# Terminada_v2_1.net
KiCad netlist of a schematic drawn in EAGLE
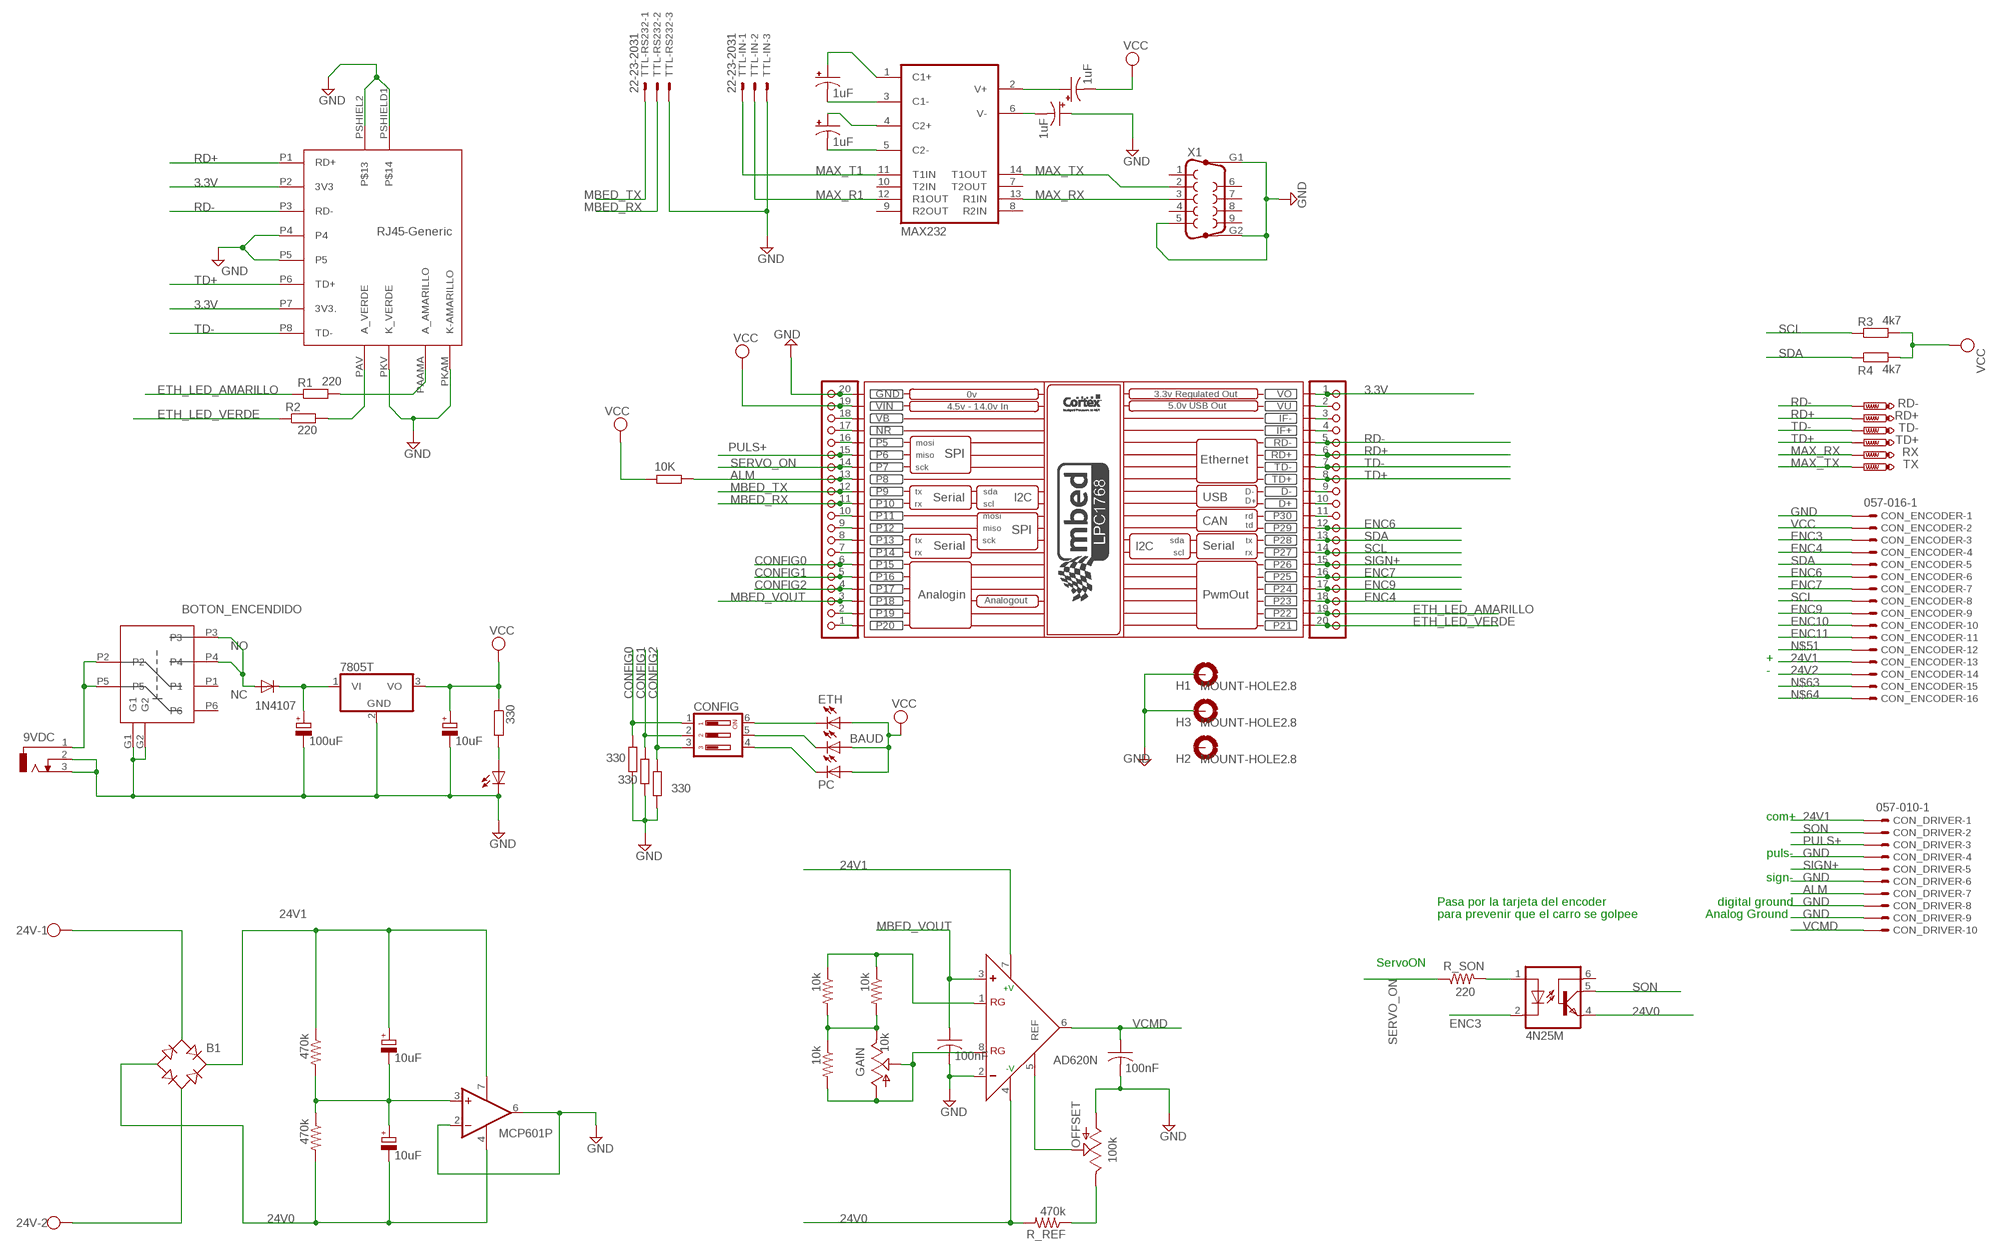
[diagram p0: schematic, sheet 1]

(export (version "E")
  (design (tool "Eeschema 10.0.6"))
  (components
    (comp (ref "9VDC")
      (value "DCJ0303")
      (footprint "eagle-import:DCJ0303")
      (libsource (lib "eagle-import") (part "DCJ0303"))
    )
    (comp (ref "24V")
      (value "W237-02P")
      (footprint "eagle-import:W237-132")
      (libsource (lib "eagle-import") (part "W237-02P"))
    )
    (comp (ref "B1")
      (value "RB1A")
      (footprint "eagle-import:RB1A")
      (libsource (lib "eagle-import") (part "RB1A"))
    )
    (comp (ref "BAUD")
      (value "LED3MM")
      (footprint "eagle-import:LED3MM")
      (libsource (lib "eagle-import") (part "LED3MM"))
    )
    (comp (ref "C1_+24")
      (value "10uF")
      (footprint "eagle-import:TT5D7")
      (libsource (lib "eagle-import") (part "CPOL-EUTT5D7"))
    )
    (comp (ref "C1_9V")
      (value "100uF")
      (footprint "eagle-import:TT5D7")
      (libsource (lib "eagle-import") (part "CPOL-EUTT5D7"))
    )
    (comp (ref "C1_MAX")
      (value "1uF")
      (footprint "eagle-import:E2,5-6E")
      (libsource (lib "eagle-import") (part "CPOL-USE2,5-6E"))
    )
    (comp (ref "C2_0V")
      (value "10uF")
      (footprint "eagle-import:TT5D7")
      (libsource (lib "eagle-import") (part "CPOL-EUTT5D7"))
    )
    (comp (ref "C2_9V")
      (value "10uF")
      (footprint "eagle-import:TT5D7")
      (libsource (lib "eagle-import") (part "CPOL-EUTT5D7"))
    )
    (comp (ref "C2_MAX")
      (value "1uF")
      (footprint "eagle-import:E2,5-6E")
      (libsource (lib "eagle-import") (part "CPOL-USE2,5-6E"))
    )
    (comp (ref "C3_AOUT")
      (value "100nF")
      (footprint "eagle-import:C025-024X044")
      (libsource (lib "eagle-import") (part "C-US025-024X044"))
    )
    (comp (ref "C3_MAX")
      (value "1uF")
      (footprint "eagle-import:E2,5-6E")
      (libsource (lib "eagle-import") (part "CPOL-USE2,5-6E"))
    )
    (comp (ref "C4_MAX")
      (value "1uF")
      (footprint "eagle-import:E2,5-6E")
      (libsource (lib "eagle-import") (part "CPOL-USE2,5-6E"))
    )
    (comp (ref "C5_AOUT")
      (value "100nF")
      (footprint "eagle-import:C025-024X044")
      (libsource (lib "eagle-import") (part "C-US025-024X044"))
    )
    (comp (ref "CONFIG")
      (value "DIP03YL")
      (footprint "eagle-import:DIP03YL")
      (libsource (lib "eagle-import") (part "DIP03YL"))
    )
    (comp (ref "CON_DRIVER")
      (value "057-010-1")
      (footprint "eagle-import:057-010-1")
      (libsource (lib "eagle-import") (part "057-010-1"))
    )
    (comp (ref "CON_ENCODER")
      (value "057-016-1")
      (footprint "eagle-import:057-016-1")
      (libsource (lib "eagle-import") (part "057-016-1"))
    )
    (comp (ref "D1_INPUT")
      (value "1N4107")
      (footprint "eagle-import:DO35-10")
      (libsource (lib "eagle-import") (part "1N4148DO35-10"))
    )
    (comp (ref "ETH")
      (value "LED3MM")
      (footprint "eagle-import:LED3MM")
      (libsource (lib "eagle-import") (part "LED3MM"))
    )
    (comp (ref "GAIN")
      (value "10k")
      (footprint "eagle-import:RJ9W")
      (libsource (lib "eagle-import") (part "TRIM_US-RJ9W"))
    )
    (comp (ref "H1")
      (value "MOUNT-HOLE2.8")
      (footprint "eagle-import:3,3-PAD")
      (libsource (lib "eagle-import") (part "MOUNT-PAD-ROUND3.3"))
    )
    (comp (ref "H2")
      (value "MOUNT-HOLE2.8")
      (footprint "eagle-import:3,3-PAD")
      (libsource (lib "eagle-import") (part "MOUNT-PAD-ROUND3.3"))
    )
    (comp (ref "H3")
      (value "MOUNT-HOLE2.8")
      (footprint "eagle-import:3,3-PAD")
      (libsource (lib "eagle-import") (part "MOUNT-PAD-ROUND3.3"))
    )
    (comp (ref "IC1")
      (value "MAX232")
      (footprint "eagle-import:DIL16")
      (libsource (lib "eagle-import") (part "MAX232"))
    )
    (comp (ref "IC2")
      (value "7805T")
      (footprint "eagle-import:TO220H")
      (libsource (lib "eagle-import") (part "78T05"))
    )
    (comp (ref "IC3")
      (value "MCP601P")
      (footprint "eagle-import:DIL08")
      (libsource (lib "eagle-import") (part "MCP601P"))
    )
    (comp (ref "IC4")
      (value "AD620N")
      (footprint "eagle-import:DIL08")
      (libsource (lib "eagle-import") (part "AD620N"))
    )
    (comp (ref "JP_LEFT")
      (value "PINHD-1X20")
      (footprint "eagle-import:1X20")
      (libsource (lib "eagle-import") (part "PINHD-1X20"))
    )
    (comp (ref "JP_RIGHT")
      (value "PINHD-1X20")
      (footprint "eagle-import:1X20")
      (libsource (lib "eagle-import") (part "PINHD-1X20"))
    )
    (comp (ref "KIT1")
      (value "MBED_NXP_LPC1768")
      (footprint "eagle-import:MBED-KIT")
      (libsource (lib "eagle-import") (part "MBED_NXP_LPC1768"))
    )
    (comp (ref "OFFSET")
      (value "100k")
      (footprint "eagle-import:RJ9W")
      (libsource (lib "eagle-import") (part "TRIM_US-RJ9W"))
    )
    (comp (ref "OK1")
      (value "4N25M")
      (footprint "eagle-import:DIL06")
      (libsource (lib "eagle-import") (part "4N?M25"))
    )
    (comp (ref "ON/OFF")
      (value "BOTON_ENCENDIDO")
      (footprint "eagle-import:BOTON_ENCNEDIDO")
      (libsource (lib "eagle-import") (part "BOTON_ENCENDIDO"))
    )
    (comp (ref "PC")
      (value "LED3MM")
      (footprint "eagle-import:LED3MM")
      (libsource (lib "eagle-import") (part "LED3MM"))
    )
    (comp (ref "POWER")
      (value "LED3MM")
      (footprint "eagle-import:LED3MM")
      (libsource (lib "eagle-import") (part "LED3MM"))
    )
    (comp (ref "PWR_LED_R")
      (value "330")
      (footprint "eagle-import:0204_7")
      (libsource (lib "eagle-import") (part "R-EU_0204/7"))
    )
    (comp (ref "R1")
      (value "220")
      (footprint "eagle-import:0207_15")
      (libsource (lib "eagle-import") (part "R-EU_0207/15"))
    )
    (comp (ref "R1_DIV")
      (value "470k")
      (footprint "eagle-import:0207_10")
      (libsource (lib "eagle-import") (part "resistor_R-US_0207/10"))
    )
    (comp (ref "R1_G")
      (value "10k")
      (footprint "eagle-import:0204_7")
      (libsource (lib "eagle-import") (part "resistor_R-US_0204/7"))
    )
    (comp (ref "R2")
      (value "220")
      (footprint "eagle-import:0207_15")
      (libsource (lib "eagle-import") (part "R-EU_0207/15"))
    )
    (comp (ref "R2_DIV")
      (value "470k")
      (footprint "eagle-import:0207_10")
      (libsource (lib "eagle-import") (part "resistor_R-US_0207/10"))
    )
    (comp (ref "R2_G")
      (value "10k")
      (footprint "eagle-import:0204_7")
      (libsource (lib "eagle-import") (part "resistor_R-US_0204/7"))
    )
    (comp (ref "R3")
      (value "4k7")
      (footprint "eagle-import:0204_7")
      (libsource (lib "eagle-import") (part "R-EU_0204/7"))
    )
    (comp (ref "R3_G")
      (value "10k")
      (footprint "eagle-import:0204_7")
      (libsource (lib "eagle-import") (part "resistor_R-US_0204/7"))
    )
    (comp (ref "R4")
      (value "4k7")
      (footprint "eagle-import:0204_7")
      (libsource (lib "eagle-import") (part "R-EU_0204/7"))
    )
    (comp (ref "R13")
      (value "330")
      (footprint "eagle-import:0204_7")
      (libsource (lib "eagle-import") (part "R-EU_0204/7"))
    )
    (comp (ref "R14")
      (value "330")
      (footprint "eagle-import:0204_7")
      (libsource (lib "eagle-import") (part "R-EU_0204/7"))
    )
    (comp (ref "R15")
      (value "330")
      (footprint "eagle-import:0204_7")
      (libsource (lib "eagle-import") (part "R-EU_0204/7"))
    )
    (comp (ref "R16_ALM")
      (value "10K")
      (footprint "eagle-import:0207_12")
      (libsource (lib "eagle-import") (part "R-EU_0207/12"))
    )
    (comp (ref "RD+")
      (value "PTR1PAD1-13Y")
      (footprint "eagle-import:P1-13Y")
      (libsource (lib "eagle-import") (part "PTR1PAD1-13Y"))
    )
    (comp (ref "RD-")
      (value "PTR1PAD1-13Y")
      (footprint "eagle-import:P1-13Y")
      (libsource (lib "eagle-import") (part "PTR1PAD1-13Y"))
    )
    (comp (ref "RX")
      (value "PTR1PAD1-13Y")
      (footprint "eagle-import:P1-13Y")
      (libsource (lib "eagle-import") (part "PTR1PAD1-13Y"))
    )
    (comp (ref "R_REF")
      (value "470k")
      (footprint "eagle-import:0204_7")
      (libsource (lib "eagle-import") (part "resistor_R-US_0204/7"))
    )
    (comp (ref "R_SON")
      (value "220")
      (footprint "eagle-import:0207_7")
      (libsource (lib "eagle-import") (part "R-US_0207/7"))
    )
    (comp (ref "TD+")
      (value "PTR1PAD1-13Y")
      (footprint "eagle-import:P1-13Y")
      (libsource (lib "eagle-import") (part "PTR1PAD1-13Y"))
    )
    (comp (ref "TD-")
      (value "PTR1PAD1-13Y")
      (footprint "eagle-import:P1-13Y")
      (libsource (lib "eagle-import") (part "PTR1PAD1-13Y"))
    )
    (comp (ref "TTL-IN")
      (value "22-23-2031")
      (footprint "eagle-import:22-23-2031")
      (fields (field (name "MF") "MOLEX"))
      (libsource (lib "eagle-import") (part "22-23-2031"))
    )
    (comp (ref "TTL-RS232")
      (value "22-23-2031")
      (footprint "eagle-import:22-23-2031")
      (fields (field (name "MF") "MOLEX"))
      (libsource (lib "eagle-import") (part "22-23-2031"))
    )
    (comp (ref "TX")
      (value "PTR1PAD1-13Y")
      (footprint "eagle-import:P1-13Y")
      (libsource (lib "eagle-import") (part "PTR1PAD1-13Y"))
    )
    (comp (ref "U$1")
      (value "RJ-45-GENERIC")
      (footprint "eagle-import:RJ45-GENERIC")
      (libsource (lib "eagle-import") (part "RJ-45-GENERIC"))
    )
    (comp (ref "X1")
      (value "F09HP")
      (footprint "eagle-import:F09HP")
      (libsource (lib "eagle-import") (part "F09HP"))
    )
  )
  (nets
    (net (code "1") (name "/3.3V") (class "Default")
      (node (ref "JP_RIGHT") (pin "1") (pinfunction "1_1") (pintype "passive"))
      (node (ref "KIT1") (pin "VOUT") (pinfunction "VO_VOUT") (pintype "power_in"))
      (node (ref "U$1") (pin "P2") (pinfunction "3V3_P2") (pintype "bidirectional"))
      (node (ref "U$1") (pin "P7") (pinfunction "3V3._P7") (pintype "bidirectional"))
    )
    (net (code "2") (name "/24V0") (class "Default")
      (node (ref "B1") (pin "-") (pinfunction "-_-") (pintype "passive"))
      (node (ref "C2_0V") (pin "-") (pinfunction "-_-") (pintype "passive"))
      (node (ref "IC3") (pin "4") (pinfunction "V-_4") (pintype "power_in"))
      (node (ref "IC4") (pin "4") (pinfunction "-V_4") (pintype "power_in"))
      (node (ref "OK1") (pin "4") (pinfunction "EMI_4") (pintype "passive"))
      (node (ref "R2_DIV") (pin "2") (pinfunction "2_2") (pintype "passive"))
      (node (ref "R_REF") (pin "2") (pinfunction "2_2") (pintype "passive"))
    )
    (net (code "3") (name "/24V1") (class "Default")
      (node (ref "B1") (pin "+") (pinfunction "+_+") (pintype "passive"))
      (node (ref "C1_+24") (pin "+") (pinfunction "+_+") (pintype "passive"))
      (node (ref "CON_DRIVER") (pin "1") (pinfunction "S_1") (pintype "passive"))
      (node (ref "CON_ENCODER") (pin "13") (pinfunction "S_13") (pintype "passive"))
      (node (ref "IC3") (pin "7") (pinfunction "V+_7") (pintype "power_in"))
      (node (ref "IC4") (pin "7") (pinfunction "+V_7") (pintype "power_in"))
      (node (ref "R1_DIV") (pin "1") (pinfunction "1_1") (pintype "passive"))
    )
    (net (code "4") (name "/24V2") (class "Default")
      (node (ref "CON_ENCODER") (pin "14") (pinfunction "S_14") (pintype "passive"))
    )
    (net (code "5") (name "/ALM") (class "Default")
      (node (ref "CON_DRIVER") (pin "7") (pinfunction "S_7") (pintype "passive"))
      (node (ref "JP_LEFT") (pin "13") (pinfunction "13_13") (pintype "passive"))
      (node (ref "KIT1") (pin "P$8") (pinfunction "P8_P$8") (pintype "bidirectional"))
      (node (ref "R16_ALM") (pin "1") (pinfunction "1_1") (pintype "passive"))
    )
    (net (code "6") (name "/CONFIG0") (class "Default")
      (node (ref "CONFIG") (pin "1") (pinfunction "1_1") (pintype "passive"))
      (node (ref "JP_LEFT") (pin "6") (pinfunction "6_6") (pintype "passive"))
      (node (ref "KIT1") (pin "P$15") (pinfunction "P15_P$15") (pintype "bidirectional"))
      (node (ref "R15") (pin "2") (pinfunction "2_2") (pintype "passive"))
    )
    (net (code "7") (name "/CONFIG1") (class "Default")
      (node (ref "CONFIG") (pin "2") (pinfunction "2_2") (pintype "passive"))
      (node (ref "JP_LEFT") (pin "5") (pinfunction "5_5") (pintype "passive"))
      (node (ref "KIT1") (pin "P$16") (pinfunction "P16_P$16") (pintype "bidirectional"))
      (node (ref "R14") (pin "2") (pinfunction "2_2") (pintype "passive"))
    )
    (net (code "8") (name "/CONFIG2") (class "Default")
      (node (ref "CONFIG") (pin "3") (pinfunction "3_3") (pintype "passive"))
      (node (ref "JP_LEFT") (pin "4") (pinfunction "4_4") (pintype "passive"))
      (node (ref "KIT1") (pin "P$17") (pinfunction "P17_P$17") (pintype "bidirectional"))
      (node (ref "R13") (pin "2") (pinfunction "2_2") (pintype "passive"))
    )
    (net (code "9") (name "/ENC3") (class "Default")
      (node (ref "CON_ENCODER") (pin "3") (pinfunction "S_3") (pintype "passive"))
      (node (ref "OK1") (pin "2") (pinfunction "C_2") (pintype "passive"))
    )
    (net (code "10") (name "/ENC4") (class "Default")
      (node (ref "CON_ENCODER") (pin "4") (pinfunction "S_4") (pintype "passive"))
      (node (ref "JP_RIGHT") (pin "18") (pinfunction "18_18") (pintype "passive"))
      (node (ref "KIT1") (pin "P$23") (pinfunction "P23_P$23") (pintype "bidirectional"))
    )
    (net (code "11") (name "/ENC6") (class "Default")
      (node (ref "CON_ENCODER") (pin "6") (pinfunction "S_6") (pintype "passive"))
      (node (ref "JP_RIGHT") (pin "12") (pinfunction "12_12") (pintype "passive"))
      (node (ref "KIT1") (pin "P$29") (pinfunction "P29_P$29") (pintype "bidirectional"))
    )
    (net (code "12") (name "/ENC7") (class "Default")
      (node (ref "CON_ENCODER") (pin "7") (pinfunction "S_7") (pintype "passive"))
      (node (ref "JP_RIGHT") (pin "16") (pinfunction "16_16") (pintype "passive"))
      (node (ref "KIT1") (pin "P$25") (pinfunction "P25_P$25") (pintype "bidirectional"))
    )
    (net (code "13") (name "/ENC9") (class "Default")
      (node (ref "CON_ENCODER") (pin "9") (pinfunction "S_9") (pintype "passive"))
      (node (ref "JP_RIGHT") (pin "17") (pinfunction "17_17") (pintype "passive"))
      (node (ref "KIT1") (pin "P$24") (pinfunction "P24_P$24") (pintype "bidirectional"))
    )
    (net (code "14") (name "/ENC10") (class "Default")
      (node (ref "CON_ENCODER") (pin "10") (pinfunction "S_10") (pintype "passive"))
    )
    (net (code "15") (name "/ENC11") (class "Default")
      (node (ref "CON_ENCODER") (pin "11") (pinfunction "S_11") (pintype "passive"))
    )
    (net (code "16") (name "/ETH_LED_AMARILLO") (class "Default")
      (node (ref "JP_RIGHT") (pin "19") (pinfunction "19_19") (pintype "passive"))
      (node (ref "KIT1") (pin "P$22") (pinfunction "P22_P$22") (pintype "bidirectional"))
      (node (ref "R1") (pin "1") (pinfunction "1_1") (pintype "passive"))
    )
    (net (code "17") (name "/ETH_LED_VERDE") (class "Default")
      (node (ref "JP_RIGHT") (pin "20") (pinfunction "20_20") (pintype "passive"))
      (node (ref "KIT1") (pin "P$21") (pinfunction "P21_P$21") (pintype "bidirectional"))
      (node (ref "R2") (pin "1") (pinfunction "1_1") (pintype "passive"))
    )
    (net (code "18") (name "/MAX_R1") (class "Default")
      (node (ref "IC1") (pin "12") (pinfunction "R1OUT_12") (pintype "output"))
      (node (ref "TTL-IN") (pin "2") (pinfunction "S_2") (pintype "passive"))
    )
    (net (code "19") (name "/MAX_RX") (class "Default")
      (node (ref "IC1") (pin "13") (pinfunction "R1IN_13") (pintype "input"))
      (node (ref "RX") (pin "TP") (pinfunction "TP_TP") (pintype "input"))
      (node (ref "X1") (pin "3") (pinfunction "3_3") (pintype "passive"))
    )
    (net (code "20") (name "/MAX_T1") (class "Default")
      (node (ref "IC1") (pin "11") (pinfunction "T1IN_11") (pintype "input"))
      (node (ref "TTL-IN") (pin "1") (pinfunction "S_1") (pintype "passive"))
    )
    (net (code "21") (name "/MAX_TX") (class "Default")
      (node (ref "IC1") (pin "14") (pinfunction "T1OUT_14") (pintype "output"))
      (node (ref "TX") (pin "TP") (pinfunction "TP_TP") (pintype "input"))
      (node (ref "X1") (pin "2") (pinfunction "2_2") (pintype "passive"))
    )
    (net (code "22") (name "/MBED_RX") (class "Default")
      (node (ref "JP_LEFT") (pin "11") (pinfunction "11_11") (pintype "passive"))
      (node (ref "KIT1") (pin "P$10") (pinfunction "P10_P$10") (pintype "bidirectional"))
      (node (ref "TTL-RS232") (pin "2") (pinfunction "S_2") (pintype "passive"))
    )
    (net (code "23") (name "/MBED_TX") (class "Default")
      (node (ref "JP_LEFT") (pin "12") (pinfunction "12_12") (pintype "passive"))
      (node (ref "KIT1") (pin "P$9") (pinfunction "P9_P$9") (pintype "bidirectional"))
      (node (ref "TTL-RS232") (pin "1") (pinfunction "S_1") (pintype "passive"))
    )
    (net (code "24") (name "/MBED_VOUT") (class "Default")
      (node (ref "C5_AOUT") (pin "1") (pinfunction "1_1") (pintype "passive"))
      (node (ref "IC4") (pin "3") (pinfunction "+_3") (pintype "input"))
      (node (ref "JP_LEFT") (pin "3") (pinfunction "3_3") (pintype "passive"))
      (node (ref "KIT1") (pin "P$18") (pinfunction "P18_P$18") (pintype "bidirectional"))
    )
    (net (code "25") (name "/N$51") (class "Default")
      (node (ref "CON_ENCODER") (pin "12") (pinfunction "S_12") (pintype "passive"))
    )
    (net (code "26") (name "/N$63") (class "Default")
      (node (ref "CON_ENCODER") (pin "15") (pinfunction "S_15") (pintype "passive"))
    )
    (net (code "27") (name "/N$64") (class "Default")
      (node (ref "CON_ENCODER") (pin "16") (pinfunction "S_16") (pintype "passive"))
    )
    (net (code "28") (name "/PULS+") (class "Default")
      (node (ref "CON_DRIVER") (pin "3") (pinfunction "S_3") (pintype "passive"))
      (node (ref "JP_LEFT") (pin "15") (pinfunction "15_15") (pintype "passive"))
      (node (ref "KIT1") (pin "P$6") (pinfunction "P6_P$6") (pintype "bidirectional"))
    )
    (net (code "29") (name "/RD+") (class "Default")
      (node (ref "JP_RIGHT") (pin "6") (pinfunction "6_6") (pintype "passive"))
      (node (ref "KIT1") (pin "RD+") (pinfunction "RD+_RD+") (pintype "bidirectional"))
      (node (ref "RD+") (pin "TP") (pinfunction "TP_TP") (pintype "input"))
      (node (ref "U$1") (pin "P1") (pinfunction "RD+_P1") (pintype "bidirectional"))
    )
    (net (code "30") (name "/RD-") (class "Default")
      (node (ref "JP_RIGHT") (pin "5") (pinfunction "5_5") (pintype "passive"))
      (node (ref "KIT1") (pin "RD-") (pinfunction "RD-_RD-") (pintype "bidirectional"))
      (node (ref "RD-") (pin "TP") (pinfunction "TP_TP") (pintype "input"))
      (node (ref "U$1") (pin "P3") (pinfunction "RD-_P3") (pintype "bidirectional"))
    )
    (net (code "31") (name "/SCL") (class "Default")
      (node (ref "CON_ENCODER") (pin "8") (pinfunction "S_8") (pintype "passive"))
      (node (ref "JP_RIGHT") (pin "14") (pinfunction "14_14") (pintype "passive"))
      (node (ref "KIT1") (pin "P$27") (pinfunction "P27_P$27") (pintype "bidirectional"))
      (node (ref "R3") (pin "1") (pinfunction "1_1") (pintype "passive"))
    )
    (net (code "32") (name "/SDA") (class "Default")
      (node (ref "CON_ENCODER") (pin "5") (pinfunction "S_5") (pintype "passive"))
      (node (ref "JP_RIGHT") (pin "13") (pinfunction "13_13") (pintype "passive"))
      (node (ref "KIT1") (pin "P$28") (pinfunction "P28_P$28") (pintype "bidirectional"))
      (node (ref "R4") (pin "1") (pinfunction "1_1") (pintype "passive"))
    )
    (net (code "33") (name "/SERVO_ON") (class "Default")
      (node (ref "JP_LEFT") (pin "14") (pinfunction "14_14") (pintype "passive"))
      (node (ref "KIT1") (pin "P$7") (pinfunction "P7_P$7") (pintype "bidirectional"))
      (node (ref "R_SON") (pin "1") (pinfunction "1_1") (pintype "passive"))
    )
    (net (code "34") (name "/SIGN+") (class "Default")
      (node (ref "CON_DRIVER") (pin "5") (pinfunction "S_5") (pintype "passive"))
      (node (ref "JP_RIGHT") (pin "15") (pinfunction "15_15") (pintype "passive"))
      (node (ref "KIT1") (pin "P$26") (pinfunction "P26_P$26") (pintype "bidirectional"))
    )
    (net (code "35") (name "/SON") (class "Default")
      (node (ref "CON_DRIVER") (pin "2") (pinfunction "S_2") (pintype "passive"))
      (node (ref "OK1") (pin "5") (pinfunction "COL_5") (pintype "passive"))
    )
    (net (code "36") (name "/TD+") (class "Default")
      (node (ref "JP_RIGHT") (pin "8") (pinfunction "8_8") (pintype "passive"))
      (node (ref "KIT1") (pin "TD+") (pinfunction "TD+_TD+") (pintype "bidirectional"))
      (node (ref "TD+") (pin "TP") (pinfunction "TP_TP") (pintype "input"))
      (node (ref "U$1") (pin "P6") (pinfunction "TD+_P6") (pintype "bidirectional"))
    )
    (net (code "37") (name "/TD-") (class "Default")
      (node (ref "JP_RIGHT") (pin "7") (pinfunction "7_7") (pintype "passive"))
      (node (ref "KIT1") (pin "TD-") (pinfunction "TD-_TD-") (pintype "bidirectional"))
      (node (ref "TD-") (pin "TP") (pinfunction "TP_TP") (pintype "input"))
      (node (ref "U$1") (pin "P8") (pinfunction "TD-_P8") (pintype "bidirectional"))
    )
    (net (code "38") (name "/VCMD") (class "Default")
      (node (ref "C3_AOUT") (pin "1") (pinfunction "1_1") (pintype "passive"))
      (node (ref "CON_DRIVER") (pin "10") (pinfunction "S_10") (pintype "passive"))
      (node (ref "IC4") (pin "6") (pinfunction "OUT_6") (pintype "output"))
    )
    (net (code "39") (name "GND") (class "Default")
      (node (ref "9VDC") (pin "2") (pinfunction "2_2") (pintype "passive"))
      (node (ref "9VDC") (pin "3") (pinfunction "3_3") (pintype "passive"))
      (node (ref "C1_9V") (pin "-") (pinfunction "-_-") (pintype "passive"))
      (node (ref "C2_9V") (pin "-") (pinfunction "-_-") (pintype "passive"))
      (node (ref "C3_AOUT") (pin "2") (pinfunction "2_2") (pintype "passive"))
      (node (ref "C3_MAX") (pin "+") (pinfunction "+_+") (pintype "passive"))
      (node (ref "C5_AOUT") (pin "2") (pinfunction "2_2") (pintype "passive"))
      (node (ref "CON_DRIVER") (pin "4") (pinfunction "S_4") (pintype "passive"))
      (node (ref "CON_DRIVER") (pin "6") (pinfunction "S_6") (pintype "passive"))
      (node (ref "CON_DRIVER") (pin "8") (pinfunction "S_8") (pintype "passive"))
      (node (ref "CON_DRIVER") (pin "9") (pinfunction "S_9") (pintype "passive"))
      (node (ref "CON_ENCODER") (pin "1") (pinfunction "S_1") (pintype "passive"))
      (node (ref "H1") (pin "B3,3") (pinfunction "MOUNT_B3,3") (pintype "passive"))
      (node (ref "H3") (pin "B3,3") (pinfunction "MOUNT_B3,3") (pintype "passive"))
      (node (ref "IC2") (pin "2") (pinfunction "GND_2") (pintype "passive"))
      (node (ref "IC3") (pin "2") (pinfunction "-IN_2") (pintype "input"))
      (node (ref "IC3") (pin "6") (pinfunction "OUT_6") (pintype "output"))
      (node (ref "IC4") (pin "2") (pinfunction "-_2") (pintype "input"))
      (node (ref "JP_LEFT") (pin "20") (pinfunction "20_20") (pintype "passive"))
      (node (ref "KIT1") (pin "GND") (pinfunction "GND_GND") (pintype "power_in"))
      (node (ref "OFFSET") (pin "A") (pinfunction "A_A") (pintype "passive"))
      (node (ref "ON/OFF") (pin "G1") (pinfunction "G1_G1") (pintype "bidirectional"))
      (node (ref "ON/OFF") (pin "G2") (pinfunction "G2_G2") (pintype "bidirectional"))
      (node (ref "POWER") (pin "K") (pinfunction "C_K") (pintype "passive"))
      (node (ref "R13") (pin "1") (pinfunction "1_1") (pintype "passive"))
      (node (ref "R14") (pin "1") (pinfunction "1_1") (pintype "passive"))
      (node (ref "R15") (pin "1") (pinfunction "1_1") (pintype "passive"))
      (node (ref "TTL-IN") (pin "3") (pinfunction "S_3") (pintype "passive"))
      (node (ref "TTL-RS232") (pin "3") (pinfunction "S_3") (pintype "passive"))
      (node (ref "U$1") (pin "P4") (pinfunction "P4_P4") (pintype "bidirectional"))
      (node (ref "U$1") (pin "P5") (pinfunction "P5_P5") (pintype "bidirectional"))
      (node (ref "U$1") (pin "PKAM") (pinfunction "K-AMARILLO_PKAM") (pintype "bidirectional"))
      (node (ref "U$1") (pin "PKV") (pinfunction "K_VERDE_PKV") (pintype "bidirectional"))
      (node (ref "U$1") (pin "PSHIEL2") (pinfunction "P$13_PSHIEL2") (pintype "bidirectional"))
      (node (ref "U$1") (pin "PSHIELD1") (pinfunction "P$14_PSHIELD1") (pintype "bidirectional"))
      (node (ref "X1") (pin "5") (pinfunction "5_5") (pintype "passive"))
      (node (ref "X1") (pin "G1") (pinfunction "G1_G1") (pintype "passive"))
      (node (ref "X1") (pin "G2") (pinfunction "G2_G2") (pintype "passive"))
    )
    (net (code "40") (name "Net-(9VDC-Pad1)") (class "Default")
      (node (ref "9VDC") (pin "1") (pinfunction "1_1") (pintype "passive"))
      (node (ref "ON/OFF") (pin "P2") (pinfunction "P2_P2") (pintype "bidirectional"))
      (node (ref "ON/OFF") (pin "P5") (pinfunction "P5_P5") (pintype "bidirectional"))
    )
    (net (code "41") (name "Net-(24VA-KL)") (class "Default")
      (node (ref "24V") (pin "1") (pinfunction "KL_1") (pintype "passive"))
      (node (ref "B1") (pin "AC1") (pinfunction "AC1_AC1") (pintype "passive"))
    )
    (net (code "42") (name "Net-(24VB-KL)") (class "Default")
      (node (ref "24V") (pin "2") (pinfunction "KL_2") (pintype "passive"))
      (node (ref "B1") (pin "AC2") (pinfunction "AC2_AC2") (pintype "passive"))
    )
    (net (code "43") (name "Net-(BAUD-C)") (class "Default")
      (node (ref "BAUD") (pin "K") (pinfunction "C_K") (pintype "passive"))
      (node (ref "CONFIG") (pin "5") (pinfunction "5_5") (pintype "passive"))
    )
    (net (code "44") (name "Net-(D1_INPUT-PadA)") (class "Default")
      (node (ref "D1_INPUT") (pin "A") (pinfunction "A_A") (pintype "passive"))
      (node (ref "ON/OFF") (pin "P3") (pinfunction "P3_P3") (pintype "bidirectional"))
      (node (ref "ON/OFF") (pin "P4") (pinfunction "P4_P4") (pintype "bidirectional"))
    )
    (net (code "45") (name "Net-(ETH-C)") (class "Default")
      (node (ref "CONFIG") (pin "6") (pinfunction "6_6") (pintype "passive"))
      (node (ref "ETH") (pin "K") (pinfunction "C_K") (pintype "passive"))
    )
    (net (code "46") (name "Net-(GAIN-PadA)") (class "Default")
      (node (ref "GAIN") (pin "A") (pinfunction "A_A") (pintype "passive"))
      (node (ref "GAIN") (pin "S") (pinfunction "S_S") (pintype "passive"))
      (node (ref "IC4") (pin "8") (pinfunction "RG_8") (pintype "passive"))
      (node (ref "R2_G") (pin "2") (pinfunction "2_2") (pintype "passive"))
    )
    (net (code "47") (name "Net-(GAIN-PadE)") (class "Default")
      (node (ref "GAIN") (pin "E") (pinfunction "E_E") (pintype "passive"))
      (node (ref "R1_G") (pin "2") (pinfunction "2_2") (pintype "passive"))
      (node (ref "R2_G") (pin "1") (pinfunction "1_1") (pintype "passive"))
      (node (ref "R3_G") (pin "2") (pinfunction "2_2") (pintype "passive"))
    )
    (net (code "48") (name "Net-(IC1A-C1+)") (class "Default")
      (node (ref "C1_MAX") (pin "+") (pinfunction "+_+") (pintype "passive"))
      (node (ref "IC1") (pin "1") (pinfunction "C1+_1") (pintype "bidirectional"))
    )
    (net (code "49") (name "Net-(IC1A-C1-)") (class "Default")
      (node (ref "C1_MAX") (pin "-") (pinfunction "-_-") (pintype "passive"))
      (node (ref "IC1") (pin "3") (pinfunction "C1-_3") (pintype "bidirectional"))
    )
    (net (code "50") (name "Net-(IC1A-C2+)") (class "Default")
      (node (ref "C2_MAX") (pin "+") (pinfunction "+_+") (pintype "passive"))
      (node (ref "IC1") (pin "4") (pinfunction "C2+_4") (pintype "bidirectional"))
    )
    (net (code "51") (name "Net-(IC1A-C2-)") (class "Default")
      (node (ref "C2_MAX") (pin "-") (pinfunction "-_-") (pintype "passive"))
      (node (ref "IC1") (pin "5") (pinfunction "C2-_5") (pintype "bidirectional"))
    )
    (net (code "52") (name "Net-(IC1A-V+)") (class "Default")
      (node (ref "C4_MAX") (pin "+") (pinfunction "+_+") (pintype "passive"))
      (node (ref "IC1") (pin "2") (pinfunction "V+_2") (pintype "bidirectional"))
    )
    (net (code "53") (name "Net-(IC1A-V-)") (class "Default")
      (node (ref "C3_MAX") (pin "-") (pinfunction "-_-") (pintype "passive"))
      (node (ref "IC1") (pin "6") (pinfunction "V-_6") (pintype "bidirectional"))
    )
    (net (code "54") (name "Net-(IC2-VI)") (class "Default")
      (node (ref "C1_9V") (pin "+") (pinfunction "+_+") (pintype "passive"))
      (node (ref "D1_INPUT") (pin "C") (pinfunction "C_C") (pintype "passive"))
      (node (ref "IC2") (pin "1") (pinfunction "VI_1") (pintype "input"))
    )
    (net (code "55") (name "Net-(IC3-+IN)") (class "Default")
      (node (ref "C1_+24") (pin "-") (pinfunction "-_-") (pintype "passive"))
      (node (ref "C2_0V") (pin "+") (pinfunction "+_+") (pintype "passive"))
      (node (ref "IC3") (pin "3") (pinfunction "+IN_3") (pintype "input"))
      (node (ref "R1_DIV") (pin "2") (pinfunction "2_2") (pintype "passive"))
      (node (ref "R2_DIV") (pin "1") (pinfunction "1_1") (pintype "passive"))
    )
    (net (code "56") (name "Net-(IC4-REF)") (class "Default")
      (node (ref "IC4") (pin "5") (pinfunction "REF_5") (pintype "passive"))
      (node (ref "OFFSET") (pin "S") (pinfunction "S_S") (pintype "passive"))
    )
    (net (code "57") (name "Net-(IC4-RG-Pad1)") (class "Default")
      (node (ref "IC4") (pin "1") (pinfunction "RG_1") (pintype "passive"))
      (node (ref "R1_G") (pin "1") (pinfunction "1_1") (pintype "passive"))
      (node (ref "R3_G") (pin "1") (pinfunction "1_1") (pintype "passive"))
    )
    (net (code "58") (name "Net-(JP_LEFT-Pad17)") (class "Default")
      (node (ref "JP_LEFT") (pin "17") (pinfunction "17_17") (pintype "passive"))
      (node (ref "KIT1") (pin "NR") (pinfunction "NR_NR") (pintype "power_in"))
    )
    (net (code "59") (name "Net-(JP_LEFT-Pad18)") (class "Default")
      (node (ref "JP_LEFT") (pin "18") (pinfunction "18_18") (pintype "passive"))
      (node (ref "KIT1") (pin "VB") (pinfunction "VB_VB") (pintype "power_in"))
    )
    (net (code "60") (name "Net-(JP_RIGHT-Pad2)") (class "Default")
      (node (ref "JP_RIGHT") (pin "2") (pinfunction "2_2") (pintype "passive"))
      (node (ref "KIT1") (pin "VU") (pinfunction "VU_VU") (pintype "power_in"))
    )
    (net (code "61") (name "Net-(JP_RIGHT-Pad3)") (class "Default")
      (node (ref "JP_RIGHT") (pin "3") (pinfunction "3_3") (pintype "passive"))
      (node (ref "KIT1") (pin "IF-") (pinfunction "IF-_IF-") (pintype "bidirectional"))
    )
    (net (code "62") (name "Net-(JP_RIGHT-Pad4)") (class "Default")
      (node (ref "JP_RIGHT") (pin "4") (pinfunction "4_4") (pintype "passive"))
      (node (ref "KIT1") (pin "IF+") (pinfunction "IF+_IF+") (pintype "bidirectional"))
    )
    (net (code "63") (name "Net-(JP_RIGHT-Pad9)") (class "Default")
      (node (ref "JP_RIGHT") (pin "9") (pinfunction "9_9") (pintype "passive"))
      (node (ref "KIT1") (pin "D-") (pinfunction "D-_D-") (pintype "bidirectional"))
    )
    (net (code "64") (name "Net-(JP_RIGHT-Pad10)") (class "Default")
      (node (ref "JP_RIGHT") (pin "10") (pinfunction "10_10") (pintype "passive"))
      (node (ref "KIT1") (pin "D+") (pinfunction "D+_D+") (pintype "bidirectional"))
    )
    (net (code "65") (name "Net-(KIT1-P5)") (class "Default")
      (node (ref "JP_LEFT") (pin "16") (pinfunction "16_16") (pintype "passive"))
      (node (ref "KIT1") (pin "P$5") (pinfunction "P5_P$5") (pintype "bidirectional"))
    )
    (net (code "66") (name "Net-(KIT1-P11)") (class "Default")
      (node (ref "JP_LEFT") (pin "10") (pinfunction "10_10") (pintype "passive"))
      (node (ref "KIT1") (pin "P$11") (pinfunction "P11_P$11") (pintype "bidirectional"))
    )
    (net (code "67") (name "Net-(KIT1-P12)") (class "Default")
      (node (ref "JP_LEFT") (pin "9") (pinfunction "9_9") (pintype "passive"))
      (node (ref "KIT1") (pin "P$12") (pinfunction "P12_P$12") (pintype "bidirectional"))
    )
    (net (code "68") (name "Net-(KIT1-P13)") (class "Default")
      (node (ref "JP_LEFT") (pin "8") (pinfunction "8_8") (pintype "passive"))
      (node (ref "KIT1") (pin "P$13") (pinfunction "P13_P$13") (pintype "bidirectional"))
    )
    (net (code "69") (name "Net-(KIT1-P14)") (class "Default")
      (node (ref "JP_LEFT") (pin "7") (pinfunction "7_7") (pintype "passive"))
      (node (ref "KIT1") (pin "P$14") (pinfunction "P14_P$14") (pintype "bidirectional"))
    )
    (net (code "70") (name "Net-(KIT1-P19)") (class "Default")
      (node (ref "JP_LEFT") (pin "2") (pinfunction "2_2") (pintype "passive"))
      (node (ref "KIT1") (pin "P$19") (pinfunction "P19_P$19") (pintype "bidirectional"))
    )
    (net (code "71") (name "Net-(KIT1-P20)") (class "Default")
      (node (ref "JP_LEFT") (pin "1") (pinfunction "1_1") (pintype "passive"))
      (node (ref "KIT1") (pin "P$20") (pinfunction "P20_P$20") (pintype "bidirectional"))
    )
    (net (code "72") (name "Net-(KIT1-P30)") (class "Default")
      (node (ref "JP_RIGHT") (pin "11") (pinfunction "11_11") (pintype "passive"))
      (node (ref "KIT1") (pin "P$30") (pinfunction "P30_P$30") (pintype "bidirectional"))
    )
    (net (code "73") (name "Net-(OFFSET-PadE)") (class "Default")
      (node (ref "OFFSET") (pin "E") (pinfunction "E_E") (pintype "passive"))
      (node (ref "R_REF") (pin "1") (pinfunction "1_1") (pintype "passive"))
    )
    (net (code "74") (name "Net-(OK1-A)") (class "Default")
      (node (ref "OK1") (pin "1") (pinfunction "A_1") (pintype "passive"))
      (node (ref "R_SON") (pin "2") (pinfunction "2_2") (pintype "passive"))
    )
    (net (code "75") (name "Net-(PC-C)") (class "Default")
      (node (ref "CONFIG") (pin "4") (pinfunction "4_4") (pintype "passive"))
      (node (ref "PC") (pin "K") (pinfunction "C_K") (pintype "passive"))
    )
    (net (code "76") (name "Net-(POWER-PadA)") (class "Default")
      (node (ref "POWER") (pin "A") (pinfunction "A_A") (pintype "passive"))
      (node (ref "PWR_LED_R") (pin "2") (pinfunction "2_2") (pintype "passive"))
    )
    (net (code "77") (name "Net-(U$1-A_AMARILLO)") (class "Default")
      (node (ref "R1") (pin "2") (pinfunction "2_2") (pintype "passive"))
      (node (ref "U$1") (pin "PAAMA") (pinfunction "A_AMARILLO_PAAMA") (pintype "bidirectional"))
    )
    (net (code "78") (name "Net-(U$1-A_VERDE)") (class "Default")
      (node (ref "R2") (pin "2") (pinfunction "2_2") (pintype "passive"))
      (node (ref "U$1") (pin "PAV") (pinfunction "A_VERDE_PAV") (pintype "bidirectional"))
    )
    (net (code "79") (name "VCC") (class "Default")
      (node (ref "BAUD") (pin "A") (pinfunction "A_A") (pintype "passive"))
      (node (ref "C2_9V") (pin "+") (pinfunction "+_+") (pintype "passive"))
      (node (ref "C4_MAX") (pin "-") (pinfunction "-_-") (pintype "passive"))
      (node (ref "CON_ENCODER") (pin "2") (pinfunction "S_2") (pintype "passive"))
      (node (ref "ETH") (pin "A") (pinfunction "A_A") (pintype "passive"))
      (node (ref "IC2") (pin "3") (pinfunction "VO_3") (pintype "passive"))
      (node (ref "JP_LEFT") (pin "19") (pinfunction "19_19") (pintype "passive"))
      (node (ref "KIT1") (pin "VIN") (pinfunction "VIN_VIN") (pintype "power_in"))
      (node (ref "PC") (pin "A") (pinfunction "A_A") (pintype "passive"))
      (node (ref "PWR_LED_R") (pin "1") (pinfunction "1_1") (pintype "passive"))
      (node (ref "R16_ALM") (pin "2") (pinfunction "2_2") (pintype "passive"))
      (node (ref "R3") (pin "2") (pinfunction "2_2") (pintype "passive"))
      (node (ref "R4") (pin "2") (pinfunction "2_2") (pintype "passive"))
    )
    (net (code "80") (name "unconnected-(H2-MOUNT-PadB3,3)") (class "Default")
      (node (ref "H2") (pin "B3,3") (pinfunction "MOUNT_B3,3") (pintype "passive"))
    )
    (net (code "81") (name "unconnected-(IC1A-R2IN-Pad8)") (class "Default")
      (node (ref "IC1") (pin "8") (pinfunction "R2IN_8") (pintype "input"))
    )
    (net (code "82") (name "unconnected-(IC1A-R2OUT-Pad9)") (class "Default")
      (node (ref "IC1") (pin "9") (pinfunction "R2OUT_9") (pintype "output"))
    )
    (net (code "83") (name "unconnected-(IC1A-T2IN-Pad10)") (class "Default")
      (node (ref "IC1") (pin "10") (pinfunction "T2IN_10") (pintype "input"))
    )
    (net (code "84") (name "unconnected-(IC1A-T2OUT-Pad7)") (class "Default")
      (node (ref "IC1") (pin "7") (pinfunction "T2OUT_7") (pintype "output"))
    )
    (net (code "85") (name "unconnected-(OK1-BAS-Pad6)") (class "Default")
      (node (ref "OK1") (pin "6") (pinfunction "BAS_6") (pintype "passive"))
    )
    (net (code "86") (name "unconnected-(ON/OFF-PadP1)") (class "Default")
      (node (ref "ON/OFF") (pin "P1") (pinfunction "P1_P1") (pintype "bidirectional"))
    )
    (net (code "87") (name "unconnected-(ON/OFF-PadP6)") (class "Default")
      (node (ref "ON/OFF") (pin "P6") (pinfunction "P6_P6") (pintype "bidirectional"))
    )
    (net (code "88") (name "unconnected-(X1-Pad1)") (class "Default")
      (node (ref "X1") (pin "1") (pinfunction "1_1") (pintype "passive"))
    )
    (net (code "89") (name "unconnected-(X1-Pad4)") (class "Default")
      (node (ref "X1") (pin "4") (pinfunction "4_4") (pintype "passive"))
    )
    (net (code "90") (name "unconnected-(X1-Pad6)") (class "Default")
      (node (ref "X1") (pin "6") (pinfunction "6_6") (pintype "passive"))
    )
    (net (code "91") (name "unconnected-(X1-Pad7)") (class "Default")
      (node (ref "X1") (pin "7") (pinfunction "7_7") (pintype "passive"))
    )
    (net (code "92") (name "unconnected-(X1-Pad8)") (class "Default")
      (node (ref "X1") (pin "8") (pinfunction "8_8") (pintype "passive"))
    )
    (net (code "93") (name "unconnected-(X1-Pad9)") (class "Default")
      (node (ref "X1") (pin "9") (pinfunction "9_9") (pintype "passive"))
    )
  )
)
